# kossel_mini_extruder.net
KiCad netlist of a schematic drawn in EAGLE
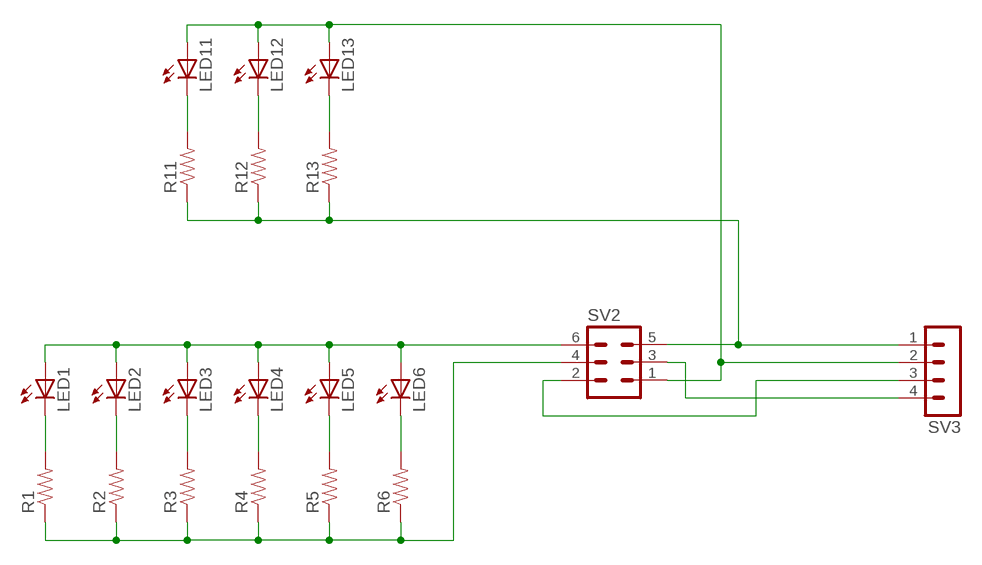
[diagram p0: schematic, sheet 1]

(export (version "E")
  (design (tool "Eeschema 10.0.6"))
  (components
    (comp (ref "LED1")
      (value "LED0805")
      (footprint "eagle-import:CHIPLED_0805")
      (libsource (lib "eagle-import") (part "LED0805"))
    )
    (comp (ref "LED2")
      (value "LED0805")
      (footprint "eagle-import:CHIPLED_0805")
      (libsource (lib "eagle-import") (part "LED0805"))
    )
    (comp (ref "LED3")
      (value "LED0805")
      (footprint "eagle-import:CHIPLED_0805")
      (libsource (lib "eagle-import") (part "LED0805"))
    )
    (comp (ref "LED4")
      (value "LED0805")
      (footprint "eagle-import:CHIPLED_0805")
      (libsource (lib "eagle-import") (part "LED0805"))
    )
    (comp (ref "LED5")
      (value "LED0805")
      (footprint "eagle-import:CHIPLED_0805")
      (libsource (lib "eagle-import") (part "LED0805"))
    )
    (comp (ref "LED6")
      (value "LED0805")
      (footprint "eagle-import:CHIPLED_0805")
      (libsource (lib "eagle-import") (part "LED0805"))
    )
    (comp (ref "LED11")
      (value "LED0805")
      (footprint "eagle-import:CHIPLED_0805")
      (libsource (lib "eagle-import") (part "LED0805"))
    )
    (comp (ref "LED12")
      (value "LED0805")
      (footprint "eagle-import:CHIPLED_0805")
      (libsource (lib "eagle-import") (part "LED0805"))
    )
    (comp (ref "LED13")
      (value "LED0805")
      (footprint "eagle-import:CHIPLED_0805")
      (libsource (lib "eagle-import") (part "LED0805"))
    )
    (comp (ref "R1")
      (value "RESISTOR0805-RES")
      (footprint "eagle-import:0805")
      (libsource (lib "eagle-import") (part "RESISTOR0805-RES"))
    )
    (comp (ref "R2")
      (value "RESISTOR0805-RES")
      (footprint "eagle-import:0805")
      (libsource (lib "eagle-import") (part "RESISTOR0805-RES"))
    )
    (comp (ref "R3")
      (value "RESISTOR0805-RES")
      (footprint "eagle-import:0805")
      (libsource (lib "eagle-import") (part "RESISTOR0805-RES"))
    )
    (comp (ref "R4")
      (value "RESISTOR0805-RES")
      (footprint "eagle-import:0805")
      (libsource (lib "eagle-import") (part "RESISTOR0805-RES"))
    )
    (comp (ref "R5")
      (value "RESISTOR0805-RES")
      (footprint "eagle-import:0805")
      (libsource (lib "eagle-import") (part "RESISTOR0805-RES"))
    )
    (comp (ref "R6")
      (value "RESISTOR0805-RES")
      (footprint "eagle-import:0805")
      (libsource (lib "eagle-import") (part "RESISTOR0805-RES"))
    )
    (comp (ref "R11")
      (value "RESISTOR0805-RES")
      (footprint "eagle-import:0805")
      (libsource (lib "eagle-import") (part "RESISTOR0805-RES"))
    )
    (comp (ref "R12")
      (value "RESISTOR0805-RES")
      (footprint "eagle-import:0805")
      (libsource (lib "eagle-import") (part "RESISTOR0805-RES"))
    )
    (comp (ref "R13")
      (value "RESISTOR0805-RES")
      (footprint "eagle-import:0805")
      (libsource (lib "eagle-import") (part "RESISTOR0805-RES"))
    )
    (comp (ref "SV2")
      (value "MA03-2")
      (footprint "eagle-import:MA03-2")
      (libsource (lib "eagle-import") (part "MA03-2"))
    )
    (comp (ref "SV3")
      (value "MA04-1")
      (footprint "eagle-import:MA04-1")
      (libsource (lib "eagle-import") (part "MA04-1"))
    )
  )
  (nets
    (net (code "1") (name "Net-(LED1-PadA)") (class "Default")
      (node (ref "LED1") (pin "A") (pinfunction "A_A") (pintype "passive"))
      (node (ref "LED2") (pin "A") (pinfunction "A_A") (pintype "passive"))
      (node (ref "LED3") (pin "A") (pinfunction "A_A") (pintype "passive"))
      (node (ref "LED4") (pin "A") (pinfunction "A_A") (pintype "passive"))
      (node (ref "LED5") (pin "A") (pinfunction "A_A") (pintype "passive"))
      (node (ref "LED6") (pin "A") (pinfunction "A_A") (pintype "passive"))
      (node (ref "SV2") (pin "6") (pinfunction "6_6") (pintype "passive"))
    )
    (net (code "2") (name "Net-(LED1-PadC)") (class "Default")
      (node (ref "LED1") (pin "C") (pinfunction "C_C") (pintype "passive"))
      (node (ref "R1") (pin "2") (pinfunction "2_2") (pintype "passive"))
    )
    (net (code "3") (name "Net-(LED2-PadC)") (class "Default")
      (node (ref "LED2") (pin "C") (pinfunction "C_C") (pintype "passive"))
      (node (ref "R2") (pin "2") (pinfunction "2_2") (pintype "passive"))
    )
    (net (code "4") (name "Net-(LED3-PadC)") (class "Default")
      (node (ref "LED3") (pin "C") (pinfunction "C_C") (pintype "passive"))
      (node (ref "R3") (pin "2") (pinfunction "2_2") (pintype "passive"))
    )
    (net (code "5") (name "Net-(LED4-PadC)") (class "Default")
      (node (ref "LED4") (pin "C") (pinfunction "C_C") (pintype "passive"))
      (node (ref "R4") (pin "2") (pinfunction "2_2") (pintype "passive"))
    )
    (net (code "6") (name "Net-(LED5-PadC)") (class "Default")
      (node (ref "LED5") (pin "C") (pinfunction "C_C") (pintype "passive"))
      (node (ref "R5") (pin "2") (pinfunction "2_2") (pintype "passive"))
    )
    (net (code "7") (name "Net-(LED6-PadC)") (class "Default")
      (node (ref "LED6") (pin "C") (pinfunction "C_C") (pintype "passive"))
      (node (ref "R6") (pin "2") (pinfunction "2_2") (pintype "passive"))
    )
    (net (code "8") (name "Net-(LED11-PadA)") (class "Default")
      (node (ref "LED11") (pin "A") (pinfunction "A_A") (pintype "passive"))
      (node (ref "LED12") (pin "A") (pinfunction "A_A") (pintype "passive"))
      (node (ref "LED13") (pin "A") (pinfunction "A_A") (pintype "passive"))
      (node (ref "SV2") (pin "1") (pinfunction "1_1") (pintype "passive"))
      (node (ref "SV3") (pin "2") (pinfunction "2_2") (pintype "passive"))
    )
    (net (code "9") (name "Net-(LED11-PadC)") (class "Default")
      (node (ref "LED11") (pin "C") (pinfunction "C_C") (pintype "passive"))
      (node (ref "R11") (pin "2") (pinfunction "2_2") (pintype "passive"))
    )
    (net (code "10") (name "Net-(LED12-PadC)") (class "Default")
      (node (ref "LED12") (pin "C") (pinfunction "C_C") (pintype "passive"))
      (node (ref "R12") (pin "2") (pinfunction "2_2") (pintype "passive"))
    )
    (net (code "11") (name "Net-(LED13-PadC)") (class "Default")
      (node (ref "LED13") (pin "C") (pinfunction "C_C") (pintype "passive"))
      (node (ref "R13") (pin "2") (pinfunction "2_2") (pintype "passive"))
    )
    (net (code "12") (name "Net-(R1-Pad1)") (class "Default")
      (node (ref "R1") (pin "1") (pinfunction "1_1") (pintype "passive"))
      (node (ref "R2") (pin "1") (pinfunction "1_1") (pintype "passive"))
      (node (ref "R3") (pin "1") (pinfunction "1_1") (pintype "passive"))
      (node (ref "R4") (pin "1") (pinfunction "1_1") (pintype "passive"))
      (node (ref "R5") (pin "1") (pinfunction "1_1") (pintype "passive"))
      (node (ref "R6") (pin "1") (pinfunction "1_1") (pintype "passive"))
      (node (ref "SV2") (pin "4") (pinfunction "4_4") (pintype "passive"))
    )
    (net (code "13") (name "Net-(R11-Pad1)") (class "Default")
      (node (ref "R11") (pin "1") (pinfunction "1_1") (pintype "passive"))
      (node (ref "R12") (pin "1") (pinfunction "1_1") (pintype "passive"))
      (node (ref "R13") (pin "1") (pinfunction "1_1") (pintype "passive"))
      (node (ref "SV2") (pin "5") (pinfunction "5_5") (pintype "passive"))
      (node (ref "SV3") (pin "1") (pinfunction "1_1") (pintype "passive"))
    )
    (net (code "14") (name "Net-(SV2-Pad2)") (class "Default")
      (node (ref "SV2") (pin "2") (pinfunction "2_2") (pintype "passive"))
      (node (ref "SV3") (pin "3") (pinfunction "3_3") (pintype "passive"))
    )
    (net (code "15") (name "Net-(SV2-Pad3)") (class "Default")
      (node (ref "SV2") (pin "3") (pinfunction "3_3") (pintype "passive"))
      (node (ref "SV3") (pin "4") (pinfunction "4_4") (pintype "passive"))
    )
  )
)
